# i2c0.net
KiCad netlist of a schematic drawn in Altium Designer
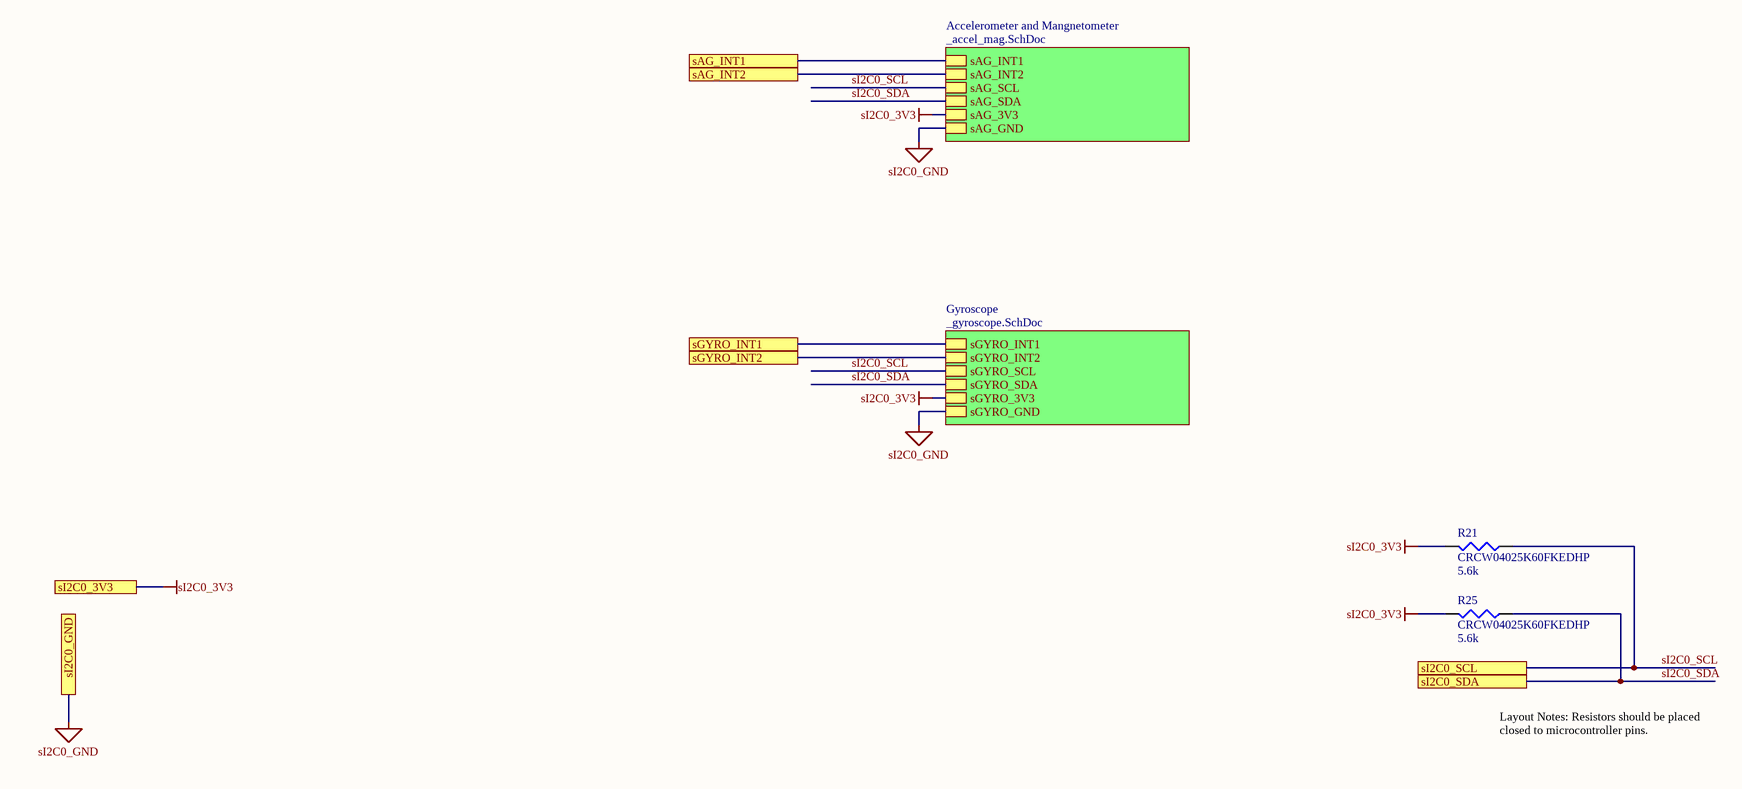
[diagram p0: _i2c0.SchDoc]

(export (version "E")
  (design (tool "Eeschema 10.0.6"))
  (components
    (comp (ref "R21")
      (value "CRCW04025K60FKEDHP")
      (footprint "0402")
      (description "0.125W, -55-155C, 1005, 50V, ±1%")
      (fields (field (name "ALTIUM_VALUE") "5.6k"))
      (libsource (lib "standard_resistors") (part "CRCW0402xxxxFKED"))
    )
    (comp (ref "R25")
      (value "CRCW04025K60FKEDHP")
      (footprint "0402")
      (description "0.125W, -55-155C, 1005, 50V, ±1%")
      (fields (field (name "ALTIUM_VALUE") "5.6k"))
      (libsource (lib "standard_resistors") (part "CRCW0402xxxxFKED"))
    )
  )
  (nets
    (net (code "5") (name "/sI2C0_SCL") (class "Default")
      (node (ref "R21") (pin "1") (pinfunction "1_1") (pintype "passive"))
    )
    (net (code "6") (name "/sI2C0_SDA") (class "Default")
      (node (ref "R25") (pin "1") (pinfunction "1_1") (pintype "passive"))
    )
    (net (code "7") (name "sI2C0_3V3") (class "Default")
      (node (ref "R21") (pin "2") (pinfunction "2_2") (pintype "passive"))
      (node (ref "R25") (pin "2") (pinfunction "2_2") (pintype "passive"))
    )
  )
)
